# Kivipallur_joonis1_mootor.net
KiCad netlist of a schematic drawn in Altium Designer
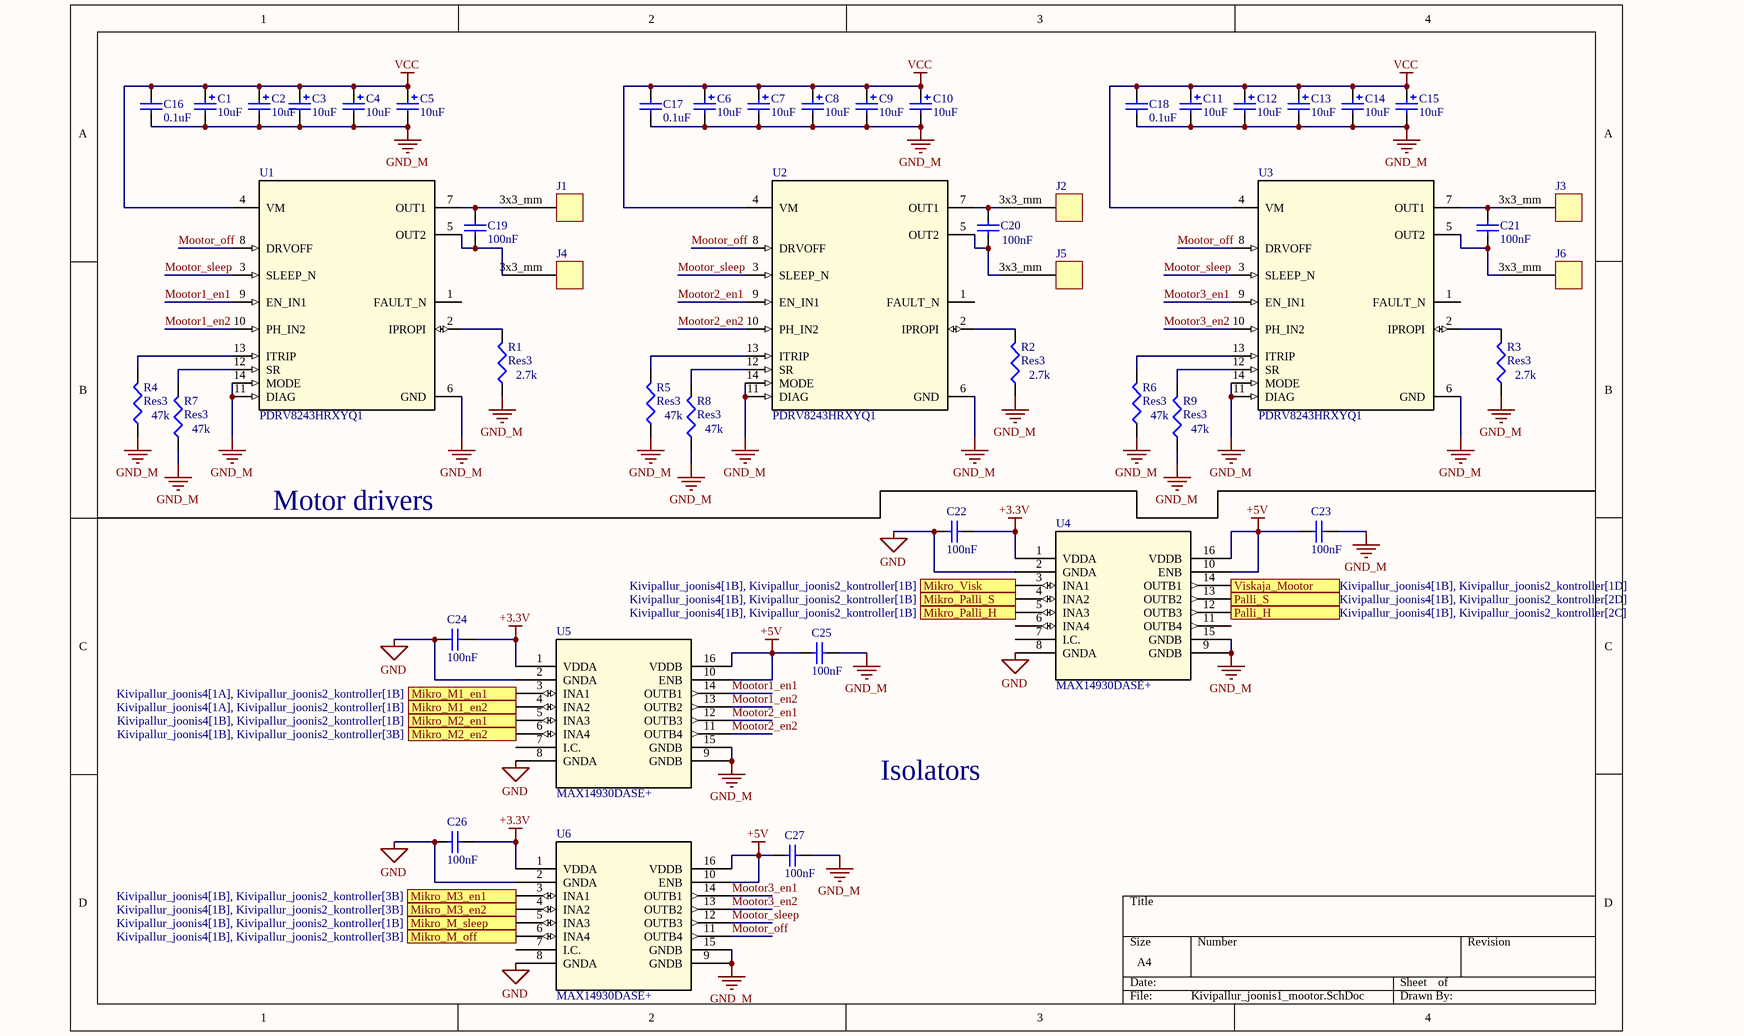
[diagram p0: Kivipallur_joonis1_mootor.SchDoc]

(export (version "E")
  (design (tool "Eeschema 10.0.6"))
  (components
    (comp (ref "C1")
      (value "10uF")
      (footprint "C0805")
      (description "Polarized Capacitor (Surface Mount)")
      (fields (field (name "Comment") "Cap Pol3") (field (name "PUBLISHER") "Altium Limited"))
      (libsource (lib "Miscellaneous Devices") (part "Cap Pol3"))
    )
    (comp (ref "C2")
      (value "10uF")
      (footprint "C0805")
      (description "Polarized Capacitor (Surface Mount)")
      (fields (field (name "Comment") "Cap Pol3") (field (name "PUBLISHER") "Altium Limited"))
      (libsource (lib "Miscellaneous Devices") (part "Cap Pol3"))
    )
    (comp (ref "C3")
      (value "10uF")
      (footprint "C0805")
      (description "Polarized Capacitor (Surface Mount)")
      (fields (field (name "Comment") "Cap Pol3") (field (name "PUBLISHER") "Altium Limited"))
      (libsource (lib "Miscellaneous Devices") (part "Cap Pol3"))
    )
    (comp (ref "C4")
      (value "10uF")
      (footprint "C0805")
      (description "Polarized Capacitor (Surface Mount)")
      (fields (field (name "Comment") "Cap Pol3") (field (name "PUBLISHER") "Altium Limited"))
      (libsource (lib "Miscellaneous Devices") (part "Cap Pol3"))
    )
    (comp (ref "C5")
      (value "10uF")
      (footprint "C0805")
      (description "Polarized Capacitor (Surface Mount)")
      (fields (field (name "Comment") "Cap Pol3") (field (name "PUBLISHER") "Altium Limited"))
      (libsource (lib "Miscellaneous Devices") (part "Cap Pol3"))
    )
    (comp (ref "C6")
      (value "10uF")
      (footprint "C0805")
      (description "Polarized Capacitor (Surface Mount)")
      (fields (field (name "Comment") "Cap Pol3") (field (name "PUBLISHER") "Altium Limited"))
      (libsource (lib "Miscellaneous Devices") (part "Cap Pol3"))
    )
    (comp (ref "C7")
      (value "10uF")
      (footprint "C0805")
      (description "Polarized Capacitor (Surface Mount)")
      (fields (field (name "Comment") "Cap Pol3") (field (name "PUBLISHER") "Altium Limited"))
      (libsource (lib "Miscellaneous Devices") (part "Cap Pol3"))
    )
    (comp (ref "C8")
      (value "10uF")
      (footprint "C0805")
      (description "Polarized Capacitor (Surface Mount)")
      (fields (field (name "Comment") "Cap Pol3") (field (name "PUBLISHER") "Altium Limited"))
      (libsource (lib "Miscellaneous Devices") (part "Cap Pol3"))
    )
    (comp (ref "C9")
      (value "10uF")
      (footprint "C0805")
      (description "Polarized Capacitor (Surface Mount)")
      (fields (field (name "Comment") "Cap Pol3") (field (name "PUBLISHER") "Altium Limited"))
      (libsource (lib "Miscellaneous Devices") (part "Cap Pol3"))
    )
    (comp (ref "C10")
      (value "10uF")
      (footprint "C0805")
      (description "Polarized Capacitor (Surface Mount)")
      (fields (field (name "Comment") "Cap Pol3") (field (name "PUBLISHER") "Altium Limited"))
      (libsource (lib "Miscellaneous Devices") (part "Cap Pol3"))
    )
    (comp (ref "C11")
      (value "10uF")
      (footprint "C0805")
      (description "Polarized Capacitor (Surface Mount)")
      (fields (field (name "Comment") "Cap Pol3") (field (name "PUBLISHER") "Altium Limited"))
      (libsource (lib "Miscellaneous Devices") (part "Cap Pol3"))
    )
    (comp (ref "C12")
      (value "10uF")
      (footprint "C0805")
      (description "Polarized Capacitor (Surface Mount)")
      (fields (field (name "Comment") "Cap Pol3") (field (name "PUBLISHER") "Altium Limited"))
      (libsource (lib "Miscellaneous Devices") (part "Cap Pol3"))
    )
    (comp (ref "C13")
      (value "10uF")
      (footprint "C0805")
      (description "Polarized Capacitor (Surface Mount)")
      (fields (field (name "Comment") "Cap Pol3") (field (name "PUBLISHER") "Altium Limited"))
      (libsource (lib "Miscellaneous Devices") (part "Cap Pol3"))
    )
    (comp (ref "C14")
      (value "10uF")
      (footprint "C0805")
      (description "Polarized Capacitor (Surface Mount)")
      (fields (field (name "Comment") "Cap Pol3") (field (name "PUBLISHER") "Altium Limited"))
      (libsource (lib "Miscellaneous Devices") (part "Cap Pol3"))
    )
    (comp (ref "C15")
      (value "10uF")
      (footprint "C0805")
      (description "Polarized Capacitor (Surface Mount)")
      (fields (field (name "Comment") "Cap Pol3") (field (name "PUBLISHER") "Altium Limited"))
      (libsource (lib "Miscellaneous Devices") (part "Cap Pol3"))
    )
    (comp (ref "C16")
      (value "0.1uF")
      (footprint "1608[0603]")
      (description "Capacitor (Semiconductor SIM Model)")
      (fields (field (name "Comment") "Cap Semi") (field (name "PUBLISHER") "Altium Limited"))
      (libsource (lib "Miscellaneous Devices") (part "Cap Semi"))
    )
    (comp (ref "C17")
      (value "0.1uF")
      (footprint "1608[0603]")
      (description "Capacitor (Semiconductor SIM Model)")
      (fields (field (name "Comment") "Cap Semi") (field (name "PUBLISHER") "Altium Limited"))
      (libsource (lib "Miscellaneous Devices") (part "Cap Semi"))
    )
    (comp (ref "C18")
      (value "0.1uF")
      (footprint "1608[0603]")
      (description "Capacitor (Semiconductor SIM Model)")
      (fields (field (name "Comment") "Cap Semi") (field (name "PUBLISHER") "Altium Limited"))
      (libsource (lib "Miscellaneous Devices") (part "Cap Semi"))
    )
    (comp (ref "C19")
      (value "100nF")
      (footprint "1608[0603]")
      (description "Capacitor (Semiconductor SIM Model)")
      (fields (field (name "Comment") "Cap Semi") (field (name "PUBLISHER") "Altium Limited"))
      (libsource (lib "Miscellaneous Devices") (part "Cap Semi"))
    )
    (comp (ref "C20")
      (value "100nF")
      (footprint "1608[0603]")
      (description "Capacitor (Semiconductor SIM Model)")
      (fields (field (name "Comment") "Cap Semi") (field (name "PUBLISHER") "Altium Limited"))
      (libsource (lib "Miscellaneous Devices") (part "Cap Semi"))
    )
    (comp (ref "C21")
      (value "100nF")
      (footprint "1608[0603]")
      (description "Capacitor (Semiconductor SIM Model)")
      (fields (field (name "Comment") "Cap Semi") (field (name "PUBLISHER") "Altium Limited"))
      (libsource (lib "Miscellaneous Devices") (part "Cap Semi"))
    )
    (comp (ref "C22")
      (value "100nF")
      (footprint "1608[0603]")
      (description "Capacitor (Semiconductor SIM Model)")
      (fields (field (name "Comment") "Cap Semi") (field (name "PUBLISHER") "Altium Limited"))
      (libsource (lib "Miscellaneous Devices") (part "Cap Semi"))
    )
    (comp (ref "C23")
      (value "100nF")
      (footprint "1608[0603]")
      (description "Capacitor (Semiconductor SIM Model)")
      (fields (field (name "Comment") "Cap Semi") (field (name "PUBLISHER") "Altium Limited"))
      (libsource (lib "Miscellaneous Devices") (part "Cap Semi"))
    )
    (comp (ref "C24")
      (value "100nF")
      (footprint "1608[0603]")
      (description "Capacitor (Semiconductor SIM Model)")
      (fields (field (name "Comment") "Cap Semi") (field (name "PUBLISHER") "Altium Limited"))
      (libsource (lib "Miscellaneous Devices") (part "Cap Semi"))
    )
    (comp (ref "C25")
      (value "100nF")
      (footprint "1608[0603]")
      (description "Capacitor (Semiconductor SIM Model)")
      (fields (field (name "Comment") "Cap Semi") (field (name "PUBLISHER") "Altium Limited"))
      (libsource (lib "Miscellaneous Devices") (part "Cap Semi"))
    )
    (comp (ref "C26")
      (value "100nF")
      (footprint "1608[0603]")
      (description "Capacitor (Semiconductor SIM Model)")
      (fields (field (name "Comment") "Cap Semi") (field (name "PUBLISHER") "Altium Limited"))
      (libsource (lib "Miscellaneous Devices") (part "Cap Semi"))
    )
    (comp (ref "C27")
      (value "100nF")
      (footprint "1608[0603]")
      (description "Capacitor (Semiconductor SIM Model)")
      (fields (field (name "Comment") "Cap Semi") (field (name "PUBLISHER") "Altium Limited"))
      (libsource (lib "Miscellaneous Devices") (part "Cap Semi"))
    )
    (comp (ref "J1") (value "3x3_mm") (footprint "3x3_mm") (libsource (lib "3x3_mm") (part "3x3_mm")))
    (comp (ref "J2") (value "3x3_mm") (footprint "3x3_mm") (libsource (lib "3x3_mm") (part "3x3_mm")))
    (comp (ref "J3") (value "3x3_mm") (footprint "3x3_mm") (libsource (lib "3x3_mm") (part "3x3_mm")))
    (comp (ref "J4") (value "3x3_mm") (footprint "3x3_mm") (libsource (lib "3x3_mm") (part "3x3_mm")))
    (comp (ref "J5") (value "3x3_mm") (footprint "3x3_mm") (libsource (lib "3x3_mm") (part "3x3_mm")))
    (comp (ref "J6") (value "3x3_mm") (footprint "3x3_mm") (libsource (lib "3x3_mm") (part "3x3_mm")))
    (comp (ref "R1")
      (value "Res3")
      (footprint "J1-0603")
      (description "Resistor")
      (fields (field (name "ALTIUM_VALUE") "2.7k") (field (name "PUBLISHER") "Altium Limited"))
      (libsource (lib "Miscellaneous Devices") (part "Res3"))
    )
    (comp (ref "R2")
      (value "Res3")
      (footprint "J1-0603")
      (description "Resistor")
      (fields (field (name "ALTIUM_VALUE") "2.7k") (field (name "PUBLISHER") "Altium Limited"))
      (libsource (lib "Miscellaneous Devices") (part "Res3"))
    )
    (comp (ref "R3")
      (value "Res3")
      (footprint "J1-0603")
      (description "Resistor")
      (fields (field (name "ALTIUM_VALUE") "2.7k") (field (name "PUBLISHER") "Altium Limited"))
      (libsource (lib "Miscellaneous Devices") (part "Res3"))
    )
    (comp (ref "R4")
      (value "Res3")
      (footprint "J1-0603")
      (description "Resistor")
      (fields (field (name "ALTIUM_VALUE") "47k") (field (name "PUBLISHER") "Altium Limited"))
      (libsource (lib "Miscellaneous Devices") (part "Res3"))
    )
    (comp (ref "R5")
      (value "Res3")
      (footprint "J1-0603")
      (description "Resistor")
      (fields (field (name "ALTIUM_VALUE") "47k") (field (name "PUBLISHER") "Altium Limited"))
      (libsource (lib "Miscellaneous Devices") (part "Res3"))
    )
    (comp (ref "R6")
      (value "Res3")
      (footprint "J1-0603")
      (description "Resistor")
      (fields (field (name "ALTIUM_VALUE") "47k") (field (name "PUBLISHER") "Altium Limited"))
      (libsource (lib "Miscellaneous Devices") (part "Res3"))
    )
    (comp (ref "R7")
      (value "Res3")
      (footprint "J1-0603")
      (description "Resistor")
      (fields (field (name "ALTIUM_VALUE") "47k") (field (name "PUBLISHER") "Altium Limited"))
      (libsource (lib "Miscellaneous Devices") (part "Res3"))
    )
    (comp (ref "R8")
      (value "Res3")
      (footprint "J1-0603")
      (description "Resistor")
      (fields (field (name "ALTIUM_VALUE") "47k") (field (name "PUBLISHER") "Altium Limited"))
      (libsource (lib "Miscellaneous Devices") (part "Res3"))
    )
    (comp (ref "R9")
      (value "Res3")
      (footprint "J1-0603")
      (description "Resistor")
      (fields (field (name "ALTIUM_VALUE") "47k") (field (name "PUBLISHER") "Altium Limited"))
      (libsource (lib "Miscellaneous Devices") (part "Res3"))
    )
    (comp (ref "U1")
      (value "PDRV8243HRXYQ1")
      (footprint "RXY0014A-MFG")
      (description "No Description Available")
      (fields (field (name "COPYRIGHT") "Copyright (C) 2022 Ultra Librarian. All rights reserved."))
      (libsource (lib "PDRV8243HRXYQ1") (part "PDRV8243HRXYQ1"))
    )
    (comp (ref "U2")
      (value "PDRV8243HRXYQ1")
      (footprint "RXY0014A-MFG")
      (description "No Description Available")
      (fields (field (name "COPYRIGHT") "Copyright (C) 2022 Ultra Librarian. All rights reserved."))
      (libsource (lib "PDRV8243HRXYQ1") (part "PDRV8243HRXYQ1"))
    )
    (comp (ref "U3")
      (value "PDRV8243HRXYQ1")
      (footprint "RXY0014A-MFG")
      (description "No Description Available")
      (fields (field (name "COPYRIGHT") "Copyright (C) 2022 Ultra Librarian. All rights reserved."))
      (libsource (lib "PDRV8243HRXYQ1") (part "PDRV8243HRXYQ1"))
    )
    (comp (ref "U4")
      (value "MAX14930DASE+")
      (footprint "21-0041_S16+1_MXM")
      (description "No Description Available")
      (fields (field (name "COPYRIGHT") "Copyright (C) 2022 Ultra Librarian. All rights reserved."))
      (libsource (lib "MAX14930DASE&plus_") (part "MAX14930DASE+_1"))
    )
    (comp (ref "U5")
      (value "MAX14930DASE+")
      (footprint "21-0041_S16+1_MXM")
      (description "No Description Available")
      (fields (field (name "COPYRIGHT") "Copyright (C) 2022 Ultra Librarian. All rights reserved."))
      (libsource (lib "MAX14930DASE&plus_") (part "MAX14930DASE+_1"))
    )
    (comp (ref "U6")
      (value "MAX14930DASE+")
      (footprint "21-0041_S16+1_MXM")
      (description "No Description Available")
      (fields (field (name "COPYRIGHT") "Copyright (C) 2022 Ultra Librarian. All rights reserved."))
      (libsource (lib "MAX14930DASE&plus_") (part "MAX14930DASE+_1"))
    )
  )
  (nets
    (net (code "1") (name "+3.3V") (class "Default")
      (node (ref "C22") (pin "2") (pinfunction "2_2") (pintype "passive"))
      (node (ref "C24") (pin "2") (pinfunction "2_2") (pintype "passive"))
      (node (ref "C26") (pin "2") (pinfunction "2_2") (pintype "passive"))
      (node (ref "U4") (pin "1") (pinfunction "VDDA_1") (pintype "power_in"))
      (node (ref "U5") (pin "1") (pinfunction "VDDA_1") (pintype "power_in"))
      (node (ref "U6") (pin "1") (pinfunction "VDDA_1") (pintype "power_in"))
    )
    (net (code "2") (name "+5V") (class "Default")
      (node (ref "C23") (pin "1") (pinfunction "1_1") (pintype "passive"))
      (node (ref "C25") (pin "1") (pinfunction "1_1") (pintype "passive"))
      (node (ref "C27") (pin "1") (pinfunction "1_1") (pintype "passive"))
      (node (ref "U4") (pin "10") (pinfunction "ENB_10") (pintype "passive"))
      (node (ref "U4") (pin "16") (pinfunction "VDDB_16") (pintype "power_in"))
      (node (ref "U5") (pin "10") (pinfunction "ENB_10") (pintype "passive"))
      (node (ref "U5") (pin "16") (pinfunction "VDDB_16") (pintype "power_in"))
      (node (ref "U6") (pin "10") (pinfunction "ENB_10") (pintype "passive"))
      (node (ref "U6") (pin "16") (pinfunction "VDDB_16") (pintype "power_in"))
    )
    (net (code "3") (name "/Mikro_M1_en1") (class "Default")
      (node (ref "U5") (pin "3") (pinfunction "INA1_3") (pintype "bidirectional"))
    )
    (net (code "4") (name "/Mikro_M1_en2") (class "Default")
      (node (ref "U5") (pin "4") (pinfunction "INA2_4") (pintype "bidirectional"))
    )
    (net (code "5") (name "/Mikro_M2_en1") (class "Default")
      (node (ref "U5") (pin "5") (pinfunction "INA3_5") (pintype "bidirectional"))
    )
    (net (code "6") (name "/Mikro_M2_en2") (class "Default")
      (node (ref "U5") (pin "6") (pinfunction "INA4_6") (pintype "bidirectional"))
    )
    (net (code "7") (name "/Mikro_M3_en1") (class "Default")
      (node (ref "U6") (pin "3") (pinfunction "INA1_3") (pintype "bidirectional"))
    )
    (net (code "8") (name "/Mikro_M3_en2") (class "Default")
      (node (ref "U6") (pin "4") (pinfunction "INA2_4") (pintype "bidirectional"))
    )
    (net (code "9") (name "/Mikro_M_off") (class "Default")
      (node (ref "U6") (pin "6") (pinfunction "INA4_6") (pintype "bidirectional"))
    )
    (net (code "10") (name "/Mikro_M_sleep") (class "Default")
      (node (ref "U6") (pin "5") (pinfunction "INA3_5") (pintype "bidirectional"))
    )
    (net (code "11") (name "/Mikro_Palli_H") (class "Default")
      (node (ref "U4") (pin "5") (pinfunction "INA3_5") (pintype "bidirectional"))
    )
    (net (code "12") (name "/Mikro_Palli_S") (class "Default")
      (node (ref "U4") (pin "4") (pinfunction "INA2_4") (pintype "bidirectional"))
    )
    (net (code "13") (name "/Mikro_Visk") (class "Default")
      (node (ref "U4") (pin "3") (pinfunction "INA1_3") (pintype "bidirectional"))
    )
    (net (code "14") (name "/Mootor1_en1") (class "Default")
      (node (ref "U1") (pin "9") (pinfunction "EN_IN1_9") (pintype "input"))
      (node (ref "U5") (pin "14") (pinfunction "OUTB1_14") (pintype "output"))
    )
    (net (code "15") (name "/Mootor1_en2") (class "Default")
      (node (ref "U1") (pin "10") (pinfunction "PH_IN2_10") (pintype "input"))
      (node (ref "U5") (pin "13") (pinfunction "OUTB2_13") (pintype "output"))
    )
    (net (code "16") (name "/Mootor2_en1") (class "Default")
      (node (ref "U2") (pin "9") (pinfunction "EN_IN1_9") (pintype "input"))
      (node (ref "U5") (pin "12") (pinfunction "OUTB3_12") (pintype "output"))
    )
    (net (code "17") (name "/Mootor2_en2") (class "Default")
      (node (ref "U2") (pin "10") (pinfunction "PH_IN2_10") (pintype "input"))
      (node (ref "U5") (pin "11") (pinfunction "OUTB4_11") (pintype "output"))
    )
    (net (code "18") (name "/Mootor3_en1") (class "Default")
      (node (ref "U3") (pin "9") (pinfunction "EN_IN1_9") (pintype "input"))
      (node (ref "U6") (pin "14") (pinfunction "OUTB1_14") (pintype "output"))
    )
    (net (code "19") (name "/Mootor3_en2") (class "Default")
      (node (ref "U3") (pin "10") (pinfunction "PH_IN2_10") (pintype "input"))
      (node (ref "U6") (pin "13") (pinfunction "OUTB2_13") (pintype "output"))
    )
    (net (code "20") (name "/Mootor_off") (class "Default")
      (node (ref "U1") (pin "8") (pinfunction "DRVOFF_8") (pintype "input"))
      (node (ref "U2") (pin "8") (pinfunction "DRVOFF_8") (pintype "input"))
      (node (ref "U3") (pin "8") (pinfunction "DRVOFF_8") (pintype "input"))
      (node (ref "U6") (pin "11") (pinfunction "OUTB4_11") (pintype "output"))
    )
    (net (code "21") (name "/Mootor_sleep") (class "Default")
      (node (ref "U1") (pin "3") (pinfunction "SLEEP_N_3") (pintype "input"))
      (node (ref "U2") (pin "3") (pinfunction "SLEEP_N_3") (pintype "input"))
      (node (ref "U3") (pin "3") (pinfunction "SLEEP_N_3") (pintype "input"))
      (node (ref "U6") (pin "12") (pinfunction "OUTB3_12") (pintype "output"))
    )
    (net (code "22") (name "/Palli_H") (class "Default")
      (node (ref "U4") (pin "12") (pinfunction "OUTB3_12") (pintype "output"))
    )
    (net (code "23") (name "/Palli_S") (class "Default")
      (node (ref "U4") (pin "13") (pinfunction "OUTB2_13") (pintype "output"))
    )
    (net (code "24") (name "/Viskaja_Mootor") (class "Default")
      (node (ref "U4") (pin "14") (pinfunction "OUTB1_14") (pintype "output"))
    )
    (net (code "25") (name "GND") (class "Default")
      (node (ref "C22") (pin "1") (pinfunction "1_1") (pintype "passive"))
      (node (ref "C24") (pin "1") (pinfunction "1_1") (pintype "passive"))
      (node (ref "C26") (pin "1") (pinfunction "1_1") (pintype "passive"))
      (node (ref "U4") (pin "2") (pinfunction "GNDA_2") (pintype "passive"))
      (node (ref "U4") (pin "8") (pinfunction "GNDA_8") (pintype "passive"))
      (node (ref "U5") (pin "2") (pinfunction "GNDA_2") (pintype "passive"))
      (node (ref "U5") (pin "8") (pinfunction "GNDA_8") (pintype "passive"))
      (node (ref "U6") (pin "2") (pinfunction "GNDA_2") (pintype "passive"))
      (node (ref "U6") (pin "8") (pinfunction "GNDA_8") (pintype "passive"))
    )
    (net (code "26") (name "GND_M") (class "Default")
      (node (ref "C1") (pin "2") (pinfunction "2_2") (pintype "passive"))
      (node (ref "C10") (pin "2") (pinfunction "2_2") (pintype "passive"))
      (node (ref "C11") (pin "2") (pinfunction "2_2") (pintype "passive"))
      (node (ref "C12") (pin "2") (pinfunction "2_2") (pintype "passive"))
      (node (ref "C13") (pin "2") (pinfunction "2_2") (pintype "passive"))
      (node (ref "C14") (pin "2") (pinfunction "2_2") (pintype "passive"))
      (node (ref "C15") (pin "2") (pinfunction "2_2") (pintype "passive"))
      (node (ref "C16") (pin "1") (pinfunction "1_1") (pintype "passive"))
      (node (ref "C17") (pin "1") (pinfunction "1_1") (pintype "passive"))
      (node (ref "C18") (pin "1") (pinfunction "1_1") (pintype "passive"))
      (node (ref "C2") (pin "2") (pinfunction "2_2") (pintype "passive"))
      (node (ref "C23") (pin "2") (pinfunction "2_2") (pintype "passive"))
      (node (ref "C25") (pin "2") (pinfunction "2_2") (pintype "passive"))
      (node (ref "C27") (pin "2") (pinfunction "2_2") (pintype "passive"))
      (node (ref "C3") (pin "2") (pinfunction "2_2") (pintype "passive"))
      (node (ref "C4") (pin "2") (pinfunction "2_2") (pintype "passive"))
      (node (ref "C5") (pin "2") (pinfunction "2_2") (pintype "passive"))
      (node (ref "C6") (pin "2") (pinfunction "2_2") (pintype "passive"))
      (node (ref "C7") (pin "2") (pinfunction "2_2") (pintype "passive"))
      (node (ref "C8") (pin "2") (pinfunction "2_2") (pintype "passive"))
      (node (ref "C9") (pin "2") (pinfunction "2_2") (pintype "passive"))
      (node (ref "R1") (pin "1") (pinfunction "1_1") (pintype "passive"))
      (node (ref "R2") (pin "1") (pinfunction "1_1") (pintype "passive"))
      (node (ref "R3") (pin "1") (pinfunction "1_1") (pintype "passive"))
      (node (ref "R4") (pin "1") (pinfunction "1_1") (pintype "passive"))
      (node (ref "R5") (pin "1") (pinfunction "1_1") (pintype "passive"))
      (node (ref "R6") (pin "1") (pinfunction "1_1") (pintype "passive"))
      (node (ref "R7") (pin "1") (pinfunction "1_1") (pintype "passive"))
      (node (ref "R8") (pin "1") (pinfunction "1_1") (pintype "passive"))
      (node (ref "R9") (pin "1") (pinfunction "1_1") (pintype "passive"))
      (node (ref "U1") (pin "11") (pinfunction "DIAG_11") (pintype "input"))
      (node (ref "U1") (pin "14") (pinfunction "MODE_14") (pintype "input"))
      (node (ref "U1") (pin "6") (pinfunction "GND_6") (pintype "power_in"))
      (node (ref "U2") (pin "11") (pinfunction "DIAG_11") (pintype "input"))
      (node (ref "U2") (pin "14") (pinfunction "MODE_14") (pintype "input"))
      (node (ref "U2") (pin "6") (pinfunction "GND_6") (pintype "power_in"))
      (node (ref "U3") (pin "11") (pinfunction "DIAG_11") (pintype "input"))
      (node (ref "U3") (pin "14") (pinfunction "MODE_14") (pintype "input"))
      (node (ref "U3") (pin "6") (pinfunction "GND_6") (pintype "power_in"))
      (node (ref "U4") (pin "15") (pinfunction "GNDB_15") (pintype "passive"))
      (node (ref "U4") (pin "9") (pinfunction "GNDB_9") (pintype "passive"))
      (node (ref "U5") (pin "15") (pinfunction "GNDB_15") (pintype "passive"))
      (node (ref "U5") (pin "9") (pinfunction "GNDB_9") (pintype "passive"))
      (node (ref "U6") (pin "15") (pinfunction "GNDB_15") (pintype "passive"))
      (node (ref "U6") (pin "9") (pinfunction "GNDB_9") (pintype "passive"))
    )
    (net (code "27") (name "Net-(U1-IPROPI)") (class "Default")
      (node (ref "R1") (pin "2") (pinfunction "2_2") (pintype "passive"))
      (node (ref "U1") (pin "2") (pinfunction "IPROPI_2") (pintype "bidirectional"))
    )
    (net (code "28") (name "Net-(U1-ITRIP)") (class "Default")
      (node (ref "R4") (pin "2") (pinfunction "2_2") (pintype "passive"))
      (node (ref "U1") (pin "13") (pinfunction "ITRIP_13") (pintype "input"))
    )
    (net (code "29") (name "Net-(U1-OUT1)") (class "Default")
      (node (ref "C19") (pin "2") (pinfunction "2_2") (pintype "passive"))
      (node (ref "J1") (pin "3x3_mm") (pintype "power_in"))
      (node (ref "U1") (pin "7") (pinfunction "OUT1_7") (pintype "passive"))
    )
    (net (code "30") (name "Net-(U1-OUT2)") (class "Default")
      (node (ref "C19") (pin "1") (pinfunction "1_1") (pintype "passive"))
      (node (ref "J4") (pin "3x3_mm") (pintype "power_in"))
      (node (ref "U1") (pin "5") (pinfunction "OUT2_5") (pintype "passive"))
    )
    (net (code "31") (name "Net-(U1-SR)") (class "Default")
      (node (ref "R7") (pin "2") (pinfunction "2_2") (pintype "passive"))
      (node (ref "U1") (pin "12") (pinfunction "SR_12") (pintype "input"))
    )
    (net (code "32") (name "Net-(U2-IPROPI)") (class "Default")
      (node (ref "R2") (pin "2") (pinfunction "2_2") (pintype "passive"))
      (node (ref "U2") (pin "2") (pinfunction "IPROPI_2") (pintype "bidirectional"))
    )
    (net (code "33") (name "Net-(U2-ITRIP)") (class "Default")
      (node (ref "R5") (pin "2") (pinfunction "2_2") (pintype "passive"))
      (node (ref "U2") (pin "13") (pinfunction "ITRIP_13") (pintype "input"))
    )
    (net (code "34") (name "Net-(U2-OUT1)") (class "Default")
      (node (ref "C20") (pin "2") (pinfunction "2_2") (pintype "passive"))
      (node (ref "J2") (pin "3x3_mm") (pintype "power_in"))
      (node (ref "U2") (pin "7") (pinfunction "OUT1_7") (pintype "passive"))
    )
    (net (code "35") (name "Net-(U2-OUT2)") (class "Default")
      (node (ref "C20") (pin "1") (pinfunction "1_1") (pintype "passive"))
      (node (ref "J5") (pin "3x3_mm") (pintype "power_in"))
      (node (ref "U2") (pin "5") (pinfunction "OUT2_5") (pintype "passive"))
    )
    (net (code "36") (name "Net-(U2-SR)") (class "Default")
      (node (ref "R8") (pin "2") (pinfunction "2_2") (pintype "passive"))
      (node (ref "U2") (pin "12") (pinfunction "SR_12") (pintype "input"))
    )
    (net (code "37") (name "Net-(U3-IPROPI)") (class "Default")
      (node (ref "R3") (pin "2") (pinfunction "2_2") (pintype "passive"))
      (node (ref "U3") (pin "2") (pinfunction "IPROPI_2") (pintype "bidirectional"))
    )
    (net (code "38") (name "Net-(U3-ITRIP)") (class "Default")
      (node (ref "R6") (pin "2") (pinfunction "2_2") (pintype "passive"))
      (node (ref "U3") (pin "13") (pinfunction "ITRIP_13") (pintype "input"))
    )
    (net (code "39") (name "Net-(U3-OUT1)") (class "Default")
      (node (ref "C21") (pin "2") (pinfunction "2_2") (pintype "passive"))
      (node (ref "J3") (pin "3x3_mm") (pintype "power_in"))
      (node (ref "U3") (pin "7") (pinfunction "OUT1_7") (pintype "passive"))
    )
    (net (code "40") (name "Net-(U3-OUT2)") (class "Default")
      (node (ref "C21") (pin "1") (pinfunction "1_1") (pintype "passive"))
      (node (ref "J6") (pin "3x3_mm") (pintype "power_in"))
      (node (ref "U3") (pin "5") (pinfunction "OUT2_5") (pintype "passive"))
    )
    (net (code "41") (name "Net-(U3-SR)") (class "Default")
      (node (ref "R9") (pin "2") (pinfunction "2_2") (pintype "passive"))
      (node (ref "U3") (pin "12") (pinfunction "SR_12") (pintype "input"))
    )
    (net (code "42") (name "VCC") (class "Default")
      (node (ref "C1") (pin "1") (pinfunction "1_1") (pintype "passive"))
      (node (ref "C10") (pin "1") (pinfunction "1_1") (pintype "passive"))
      (node (ref "C11") (pin "1") (pinfunction "1_1") (pintype "passive"))
      (node (ref "C12") (pin "1") (pinfunction "1_1") (pintype "passive"))
      (node (ref "C13") (pin "1") (pinfunction "1_1") (pintype "passive"))
      (node (ref "C14") (pin "1") (pinfunction "1_1") (pintype "passive"))
      (node (ref "C15") (pin "1") (pinfunction "1_1") (pintype "passive"))
      (node (ref "C16") (pin "2") (pinfunction "2_2") (pintype "passive"))
      (node (ref "C17") (pin "2") (pinfunction "2_2") (pintype "passive"))
      (node (ref "C18") (pin "2") (pinfunction "2_2") (pintype "passive"))
      (node (ref "C2") (pin "1") (pinfunction "1_1") (pintype "passive"))
      (node (ref "C3") (pin "1") (pinfunction "1_1") (pintype "passive"))
      (node (ref "C4") (pin "1") (pinfunction "1_1") (pintype "passive"))
      (node (ref "C5") (pin "1") (pinfunction "1_1") (pintype "passive"))
      (node (ref "C6") (pin "1") (pinfunction "1_1") (pintype "passive"))
      (node (ref "C7") (pin "1") (pinfunction "1_1") (pintype "passive"))
      (node (ref "C8") (pin "1") (pinfunction "1_1") (pintype "passive"))
      (node (ref "C9") (pin "1") (pinfunction "1_1") (pintype "passive"))
      (node (ref "U1") (pin "4") (pinfunction "VM_4") (pintype "power_in"))
      (node (ref "U2") (pin "4") (pinfunction "VM_4") (pintype "power_in"))
      (node (ref "U3") (pin "4") (pinfunction "VM_4") (pintype "power_in"))
    )
    (net (code "43") (name "unconnected-(U1-FAULT_N-Pad1)") (class "Default")
      (node (ref "U1") (pin "1") (pinfunction "FAULT_N_1") (pintype "open_collector"))
    )
    (net (code "44") (name "unconnected-(U2-FAULT_N-Pad1)") (class "Default")
      (node (ref "U2") (pin "1") (pinfunction "FAULT_N_1") (pintype "open_collector"))
    )
    (net (code "45") (name "unconnected-(U3-FAULT_N-Pad1)") (class "Default")
      (node (ref "U3") (pin "1") (pinfunction "FAULT_N_1") (pintype "open_collector"))
    )
    (net (code "46") (name "unconnected-(U4-I.C.-Pad7)") (class "Default")
      (node (ref "U4") (pin "7") (pinfunction "I.C._7") (pintype "passive"))
    )
    (net (code "47") (name "unconnected-(U4-INA4-Pad6)") (class "Default")
      (node (ref "U4") (pin "6") (pinfunction "INA4_6") (pintype "bidirectional"))
    )
    (net (code "48") (name "unconnected-(U4-OUTB4-Pad11)") (class "Default")
      (node (ref "U4") (pin "11") (pinfunction "OUTB4_11") (pintype "output"))
    )
    (net (code "49") (name "unconnected-(U5-I.C.-Pad7)") (class "Default")
      (node (ref "U5") (pin "7") (pinfunction "I.C._7") (pintype "passive"))
    )
    (net (code "50") (name "unconnected-(U6-I.C.-Pad7)") (class "Default")
      (node (ref "U6") (pin "7") (pinfunction "I.C._7") (pintype "passive"))
    )
  )
)
